# InkTime_Schematic.net
KiCad netlist of a schematic drawn in EAGLE
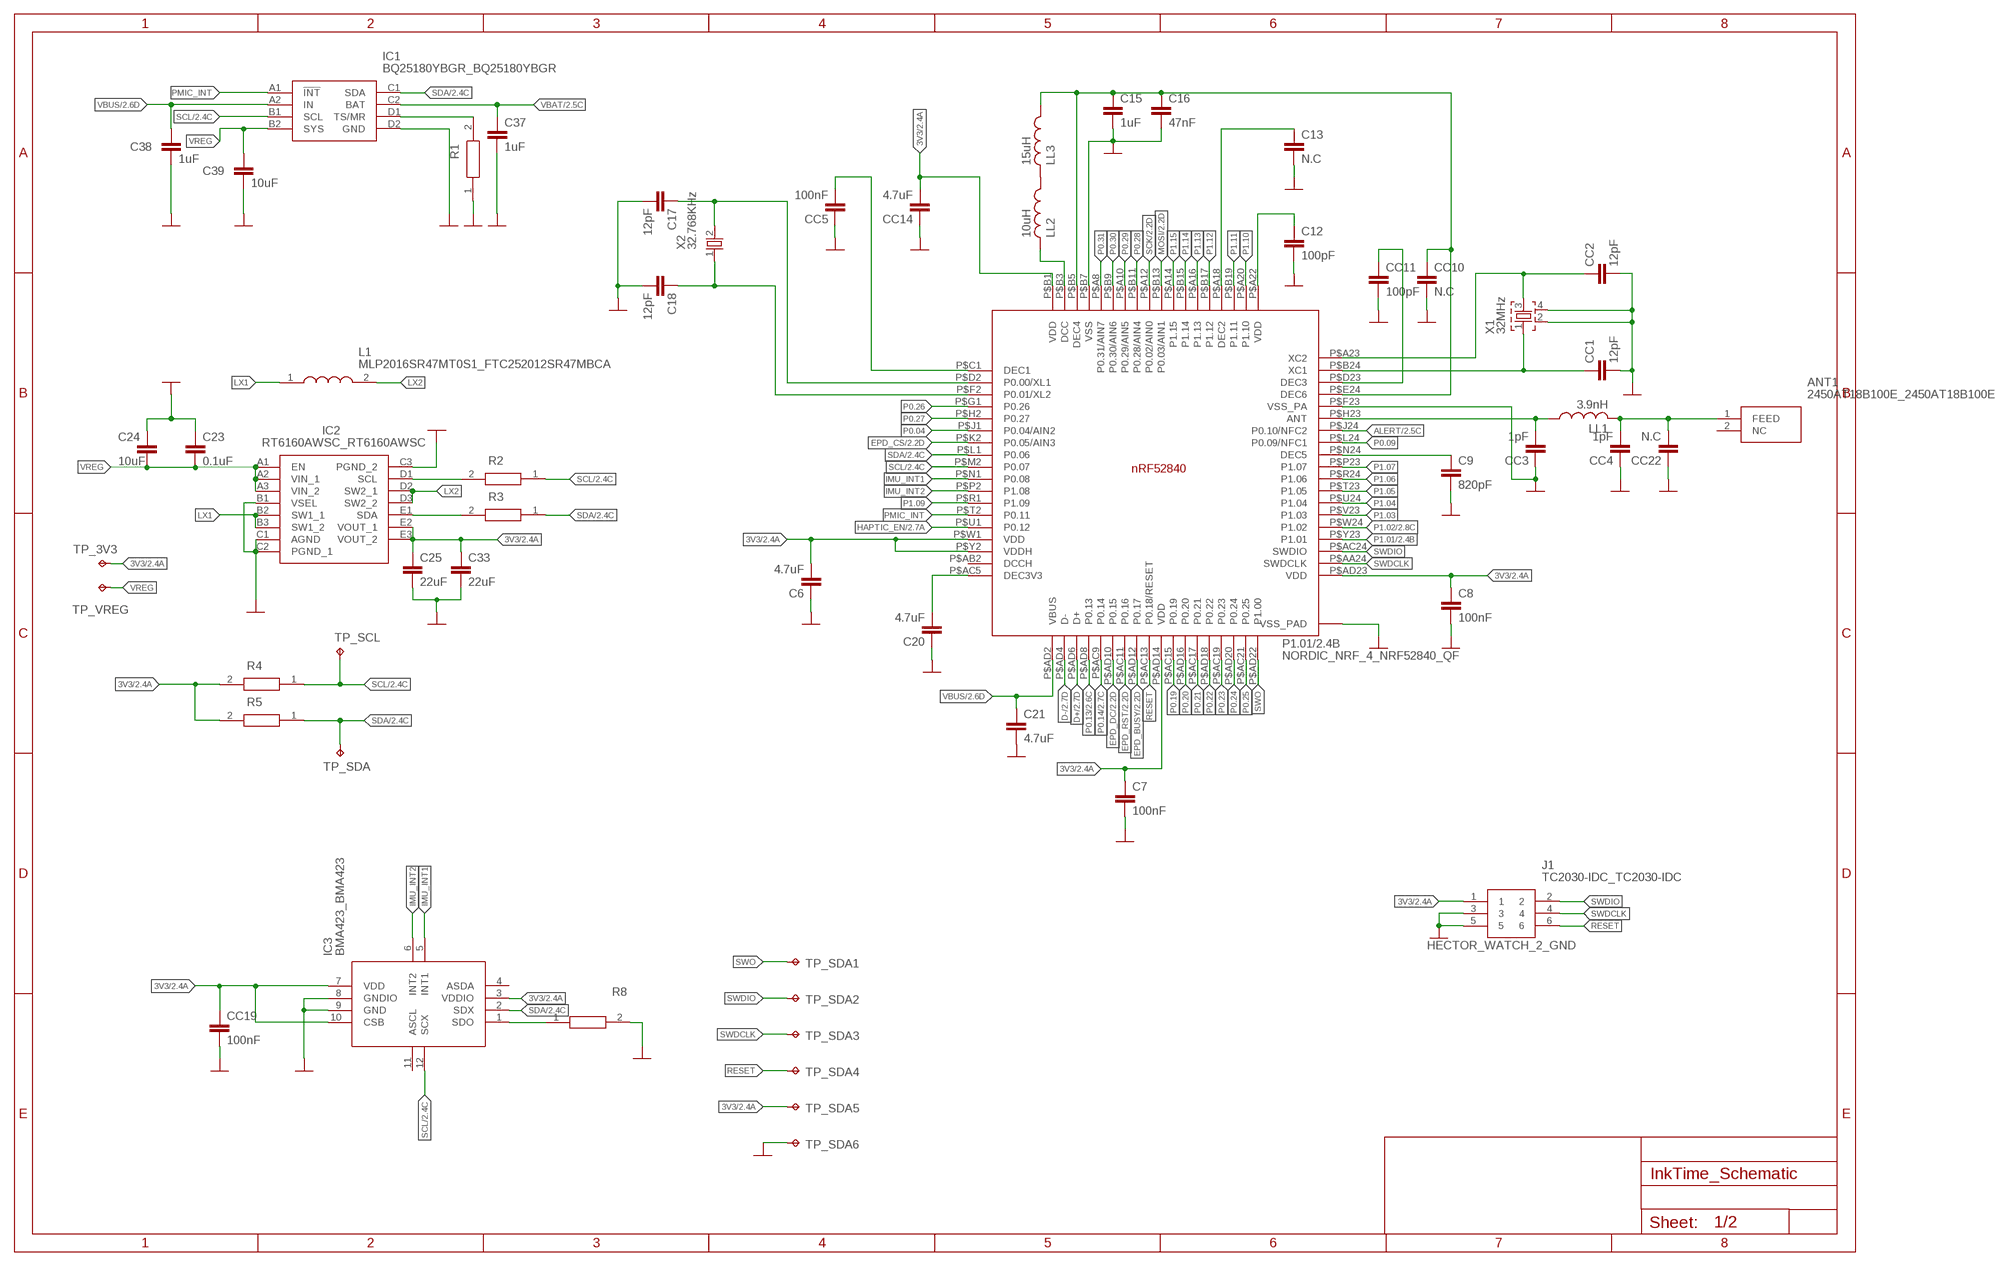
[diagram p0: schematic, sheet 1]
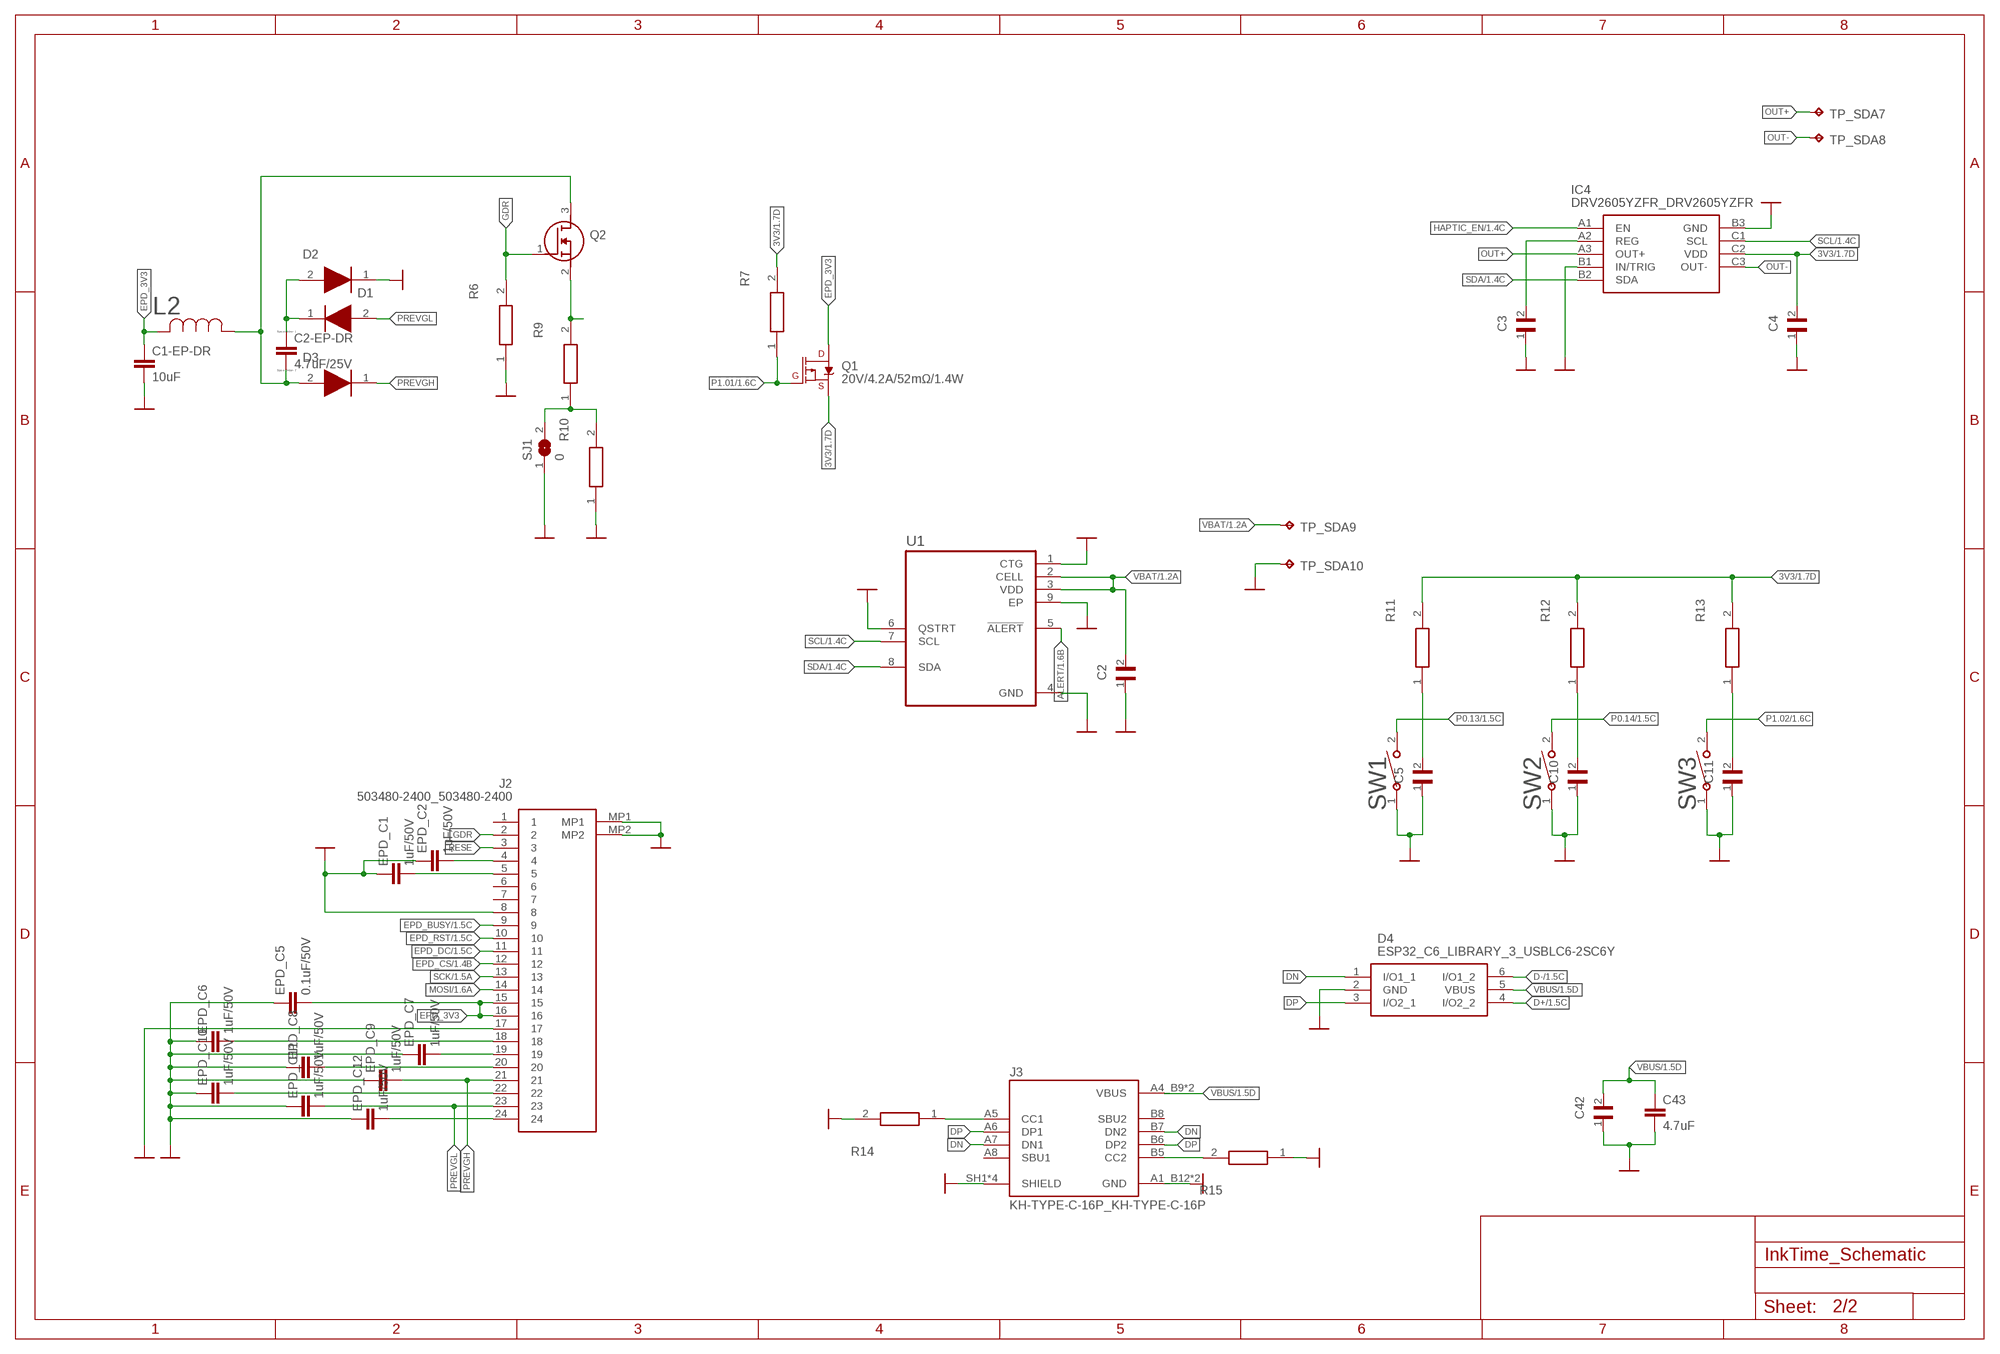
[diagram p1: schematic, sheet 2]

(export (version "E")
  (design (tool "Eeschema 10.0.6"))
  (components
    (comp (ref "ANT1")
      (value "2450AT18B100E_2450AT18B100E")
      (footprint "eagle-import:2450AT18B100E_ANTC3216X140N")
      (fields
        (field (name "ARROW_PART_NUMBER") "2450AT18B100E")
        (field (name "MOUSER_PART_NUMBER") "609-2450AT18B100E")
      )
      (libsource (lib "eagle-import") (part "2450AT18B100E_2450AT18B100E"))
    )
    (comp (ref "C6")
      (value "4.7uF")
      (footprint "eagle-import:NORDIC_NRF_3_RESC0402_M")
      (libsource (lib "eagle-import") (part "NORDIC_NRF_3_CAPACITOR_0402_M"))
    )
    (comp (ref "C7")
      (value "100nF")
      (footprint "eagle-import:NORDIC_NRF_3_RESC0402_M")
      (libsource (lib "eagle-import") (part "NORDIC_NRF_3_CAPACITOR_0402_M"))
    )
    (comp (ref "C8")
      (value "100nF")
      (footprint "eagle-import:NORDIC_NRF_3_RESC0402_M")
      (libsource (lib "eagle-import") (part "NORDIC_NRF_3_CAPACITOR_0402_M"))
    )
    (comp (ref "C9")
      (value "820pF")
      (footprint "eagle-import:NORDIC_NRF_3_RESC0402_M")
      (libsource (lib "eagle-import") (part "NORDIC_NRF_3_CAPACITOR_0402_M"))
    )
    (comp (ref "C12")
      (value "100pF")
      (footprint "eagle-import:NORDIC_NRF_3_RESC0402_M")
      (libsource (lib "eagle-import") (part "NORDIC_NRF_3_CAPACITOR_0402_M"))
    )
    (comp (ref "C13")
      (value "N.C")
      (footprint "eagle-import:NORDIC_NRF_3_RESC0402_M")
      (libsource (lib "eagle-import") (part "NORDIC_NRF_3_CAPACITOR_0402_M"))
    )
    (comp (ref "C15")
      (value "1uF")
      (footprint "eagle-import:NORDIC_NRF_3_RESC0402_M")
      (libsource (lib "eagle-import") (part "NORDIC_NRF_3_CAPACITOR_0402_M"))
    )
    (comp (ref "C16")
      (value "47nF")
      (footprint "eagle-import:NORDIC_NRF_3_RESC0402_M")
      (libsource (lib "eagle-import") (part "NORDIC_NRF_3_CAPACITOR_0402_M"))
    )
    (comp (ref "C17")
      (value "12pF")
      (footprint "eagle-import:NORDIC_NRF_3_RESC0402_M")
      (libsource (lib "eagle-import") (part "NORDIC_NRF_3_CAPACITOR_0402_M"))
    )
    (comp (ref "C18")
      (value "12pF")
      (footprint "eagle-import:NORDIC_NRF_3_RESC0402_M")
      (libsource (lib "eagle-import") (part "NORDIC_NRF_3_CAPACITOR_0402_M"))
    )
    (comp (ref "C20")
      (value "4.7uF")
      (footprint "eagle-import:NORDIC_NRF_3_RESC0402_M")
      (libsource (lib "eagle-import") (part "NORDIC_NRF_3_CAPACITOR_0402_M"))
    )
    (comp (ref "C21")
      (value "4.7uF")
      (footprint "eagle-import:NORDIC_NRF_3_RESC0402_M")
      (libsource (lib "eagle-import") (part "NORDIC_NRF_3_CAPACITOR_0402_M"))
    )
    (comp (ref "C23")
      (value "0.1uF")
      (footprint "eagle-import:NORDIC_NRF_3_RESC0402_M")
      (libsource (lib "eagle-import") (part "NORDIC_NRF_3_CAPACITOR_0402_M"))
    )
    (comp (ref "C24")
      (value "10uF")
      (footprint "eagle-import:NORDIC_NRF_3_RESC0402_M")
      (libsource (lib "eagle-import") (part "NORDIC_NRF_3_CAPACITOR_0402_M"))
    )
    (comp (ref "C25")
      (value "22uF")
      (footprint "eagle-import:NORDIC_NRF_3_RESC0402_M")
      (libsource (lib "eagle-import") (part "NORDIC_NRF_3_CAPACITOR_0402_M"))
    )
    (comp (ref "C33")
      (value "22uF")
      (footprint "eagle-import:NORDIC_NRF_3_RESC0402_M")
      (libsource (lib "eagle-import") (part "NORDIC_NRF_3_CAPACITOR_0402_M"))
    )
    (comp (ref "C37")
      (value "1uF")
      (footprint "eagle-import:NORDIC_NRF_3_RESC0402_M")
      (libsource (lib "eagle-import") (part "NORDIC_NRF_3_CAPACITOR_0402_M"))
    )
    (comp (ref "C38")
      (value "1uF")
      (footprint "eagle-import:NORDIC_NRF_3_RESC0402_M")
      (libsource (lib "eagle-import") (part "NORDIC_NRF_3_CAPACITOR_0402_M"))
    )
    (comp (ref "C39")
      (value "10uF")
      (footprint "eagle-import:NORDIC_NRF_3_RESC0402_M")
      (libsource (lib "eagle-import") (part "NORDIC_NRF_3_CAPACITOR_0402_M"))
    )
    (comp (ref "CC1")
      (value "12pF")
      (footprint "eagle-import:NORDIC_NRF_3_RESC0402_M")
      (libsource (lib "eagle-import") (part "NORDIC_NRF_3_CAPACITOR_0402_M"))
    )
    (comp (ref "CC2")
      (value "12pF")
      (footprint "eagle-import:NORDIC_NRF_3_RESC0402_M")
      (libsource (lib "eagle-import") (part "NORDIC_NRF_3_CAPACITOR_0402_M"))
    )
    (comp (ref "CC3")
      (value "1pF")
      (footprint "eagle-import:NORDIC_NRF_3_RESC0402_M")
      (libsource (lib "eagle-import") (part "NORDIC_NRF_3_CAPACITOR_0402_M"))
    )
    (comp (ref "CC4")
      (value "1pF")
      (footprint "eagle-import:NORDIC_NRF_3_RESC0402_M")
      (libsource (lib "eagle-import") (part "NORDIC_NRF_3_CAPACITOR_0402_M"))
    )
    (comp (ref "CC5")
      (value "100nF")
      (footprint "eagle-import:NORDIC_NRF_3_RESC0402_M")
      (libsource (lib "eagle-import") (part "NORDIC_NRF_3_CAPACITOR_0402_M"))
    )
    (comp (ref "CC10")
      (value "N.C")
      (footprint "eagle-import:NORDIC_NRF_3_RESC0402_M")
      (libsource (lib "eagle-import") (part "NORDIC_NRF_3_CAPACITOR_0402_M"))
    )
    (comp (ref "CC11")
      (value "100pF")
      (footprint "eagle-import:NORDIC_NRF_3_RESC0402_M")
      (libsource (lib "eagle-import") (part "NORDIC_NRF_3_CAPACITOR_0402_M"))
    )
    (comp (ref "CC14")
      (value "4.7uF")
      (footprint "eagle-import:NORDIC_NRF_3_RESC0402_M")
      (libsource (lib "eagle-import") (part "NORDIC_NRF_3_CAPACITOR_0402_M"))
    )
    (comp (ref "CC19")
      (value "100nF")
      (footprint "eagle-import:NORDIC_NRF_3_RESC0402_M")
      (libsource (lib "eagle-import") (part "NORDIC_NRF_3_CAPACITOR_0402_M"))
    )
    (comp (ref "CC22")
      (value "N.C")
      (footprint "eagle-import:NORDIC_NRF_3_RESC0402_M")
      (libsource (lib "eagle-import") (part "NORDIC_NRF_3_CAPACITOR_0402_M"))
    )
    (comp (ref "IC1")
      (value "BQ25180YBGR_BQ25180YBGR")
      (footprint "eagle-import:BQ25180YBGR_BGA8C40P2X4_100X155X50")
      (fields
        (field (name "ARROW_PART_NUMBER") "BQ25180YBGR")
        (field (name "MOUSER_PART_NUMBER") "595-BQ25180YBGR")
      )
      (libsource (lib "eagle-import") (part "BQ25180YBGR_BQ25180YBGR"))
    )
    (comp (ref "IC2")
      (value "RT6160AWSC_RT6160AWSC")
      (footprint "eagle-import:RT6160AWSC_BGA15C40P3X5_140X230X60")
      (fields
        (field (name "MANUFACTURER_PART_NUMBER") "RT6160AWSC")
        (field (name "MOUSER_PART_NUMBER") "835-RT6160AWSC")
      )
      (libsource (lib "eagle-import") (part "RT6160AWSC_RT6160AWSC"))
    )
    (comp (ref "IC3")
      (value "BMA423_BMA423")
      (footprint "eagle-import:BMA423_BMA423")
      (fields (field (name "ARROW_PART_NUMBER") "BMA423") (field (name "MOUSER_PART_NUMBER") "262-BMA423"))
      (libsource (lib "eagle-import") (part "BMA423_BMA423"))
    )
    (comp (ref "J1")
      (value "TC2030-IDC_TC2030-IDC")
      (footprint "eagle-import:TC2030-IDC_TC2030IDC")
      (fields (field (name "MANUFACTURER_PART_NUMBER") "TC2030-IDC"))
      (libsource (lib "eagle-import") (part "TC2030-IDC_TC2030-IDC"))
    )
    (comp (ref "L1")
      (value "MLP2016SR47MT0S1_FTC252012SR47MBCA")
      (footprint "eagle-import:MLP2016SR47MT0S1_INDC2016X100N")
      (fields (field (name "MANUFACTURER_PART_NUMBER") "FTC252012SR47MBCA"))
      (libsource (lib "eagle-import") (part "MLP2016SR47MT0S1_FTC252012SR47MBCA"))
    )
    (comp (ref "LL1")
      (value "3.9nH")
      (footprint "eagle-import:NORDIC_NRF_2_RESC0402_M")
      (libsource (lib "eagle-import") (part "NORDIC_NRF_2_INDUCTOR_0402_M"))
    )
    (comp (ref "LL2")
      (value "10uH")
      (footprint "eagle-import:NORDIC_NRF_2_RESC0402_M")
      (libsource (lib "eagle-import") (part "NORDIC_NRF_2_INDUCTOR_0402_M"))
    )
    (comp (ref "LL3")
      (value "15uH")
      (footprint "eagle-import:NORDIC_NRF_2_RESC0402_M")
      (libsource (lib "eagle-import") (part "NORDIC_NRF_2_INDUCTOR_0402_M"))
    )
    (comp (ref "P1.01/2.4B")
      (value "NORDIC_NRF_4_NRF52840_QF")
      (footprint "eagle-import:NORDIC_NRF_4_AQFN50P700X700X85_HS-74N")
      (libsource (lib "eagle-import") (part "NORDIC_NRF_4_NRF52840_QF"))
    )
    (comp (ref "R1")
      (value "10K")
      (footprint "eagle-import:CPF0201D7K68C1_0201")
      (libsource (lib "eagle-import") (part "CPF0201D7K68C1_CPF0201D7K68C1"))
    )
    (comp (ref "R2")
      (value "CPF0201D7K68C1_CPF0201D7K68C1")
      (footprint "eagle-import:CPF0201D7K68C1_0201")
      (libsource (lib "eagle-import") (part "CPF0201D7K68C1_CPF0201D7K68C1"))
    )
    (comp (ref "R3")
      (value "CPF0201D7K68C1_CPF0201D7K68C1")
      (footprint "eagle-import:CPF0201D7K68C1_0201")
      (libsource (lib "eagle-import") (part "CPF0201D7K68C1_CPF0201D7K68C1"))
    )
    (comp (ref "R4")
      (value "CPF0201D7K68C1_CPF0201D7K68C1")
      (footprint "eagle-import:CPF0201D7K68C1_0201")
      (libsource (lib "eagle-import") (part "CPF0201D7K68C1_CPF0201D7K68C1"))
    )
    (comp (ref "R5")
      (value "CPF0201D7K68C1_CPF0201D7K68C1")
      (footprint "eagle-import:CPF0201D7K68C1_0201")
      (libsource (lib "eagle-import") (part "CPF0201D7K68C1_CPF0201D7K68C1"))
    )
    (comp (ref "R8")
      (value "CPF0201D7K68C1_CPF0201D7K68C1")
      (footprint "eagle-import:CPF0201D7K68C1_0201")
      (libsource (lib "eagle-import") (part "CPF0201D7K68C1_CPF0201D7K68C1"))
    )
    (comp (ref "TP_3V3")
      (value "HECTOR_WATCH_1_TPTP20R")
      (footprint "eagle-import:HECTOR_WATCH_1_TP20R")
      (libsource (lib "eagle-import") (part "HECTOR_WATCH_1_TPTP20R"))
    )
    (comp (ref "TP_SCL")
      (value "HECTOR_WATCH_1_TPTP20R")
      (footprint "eagle-import:HECTOR_WATCH_1_TP20R")
      (libsource (lib "eagle-import") (part "HECTOR_WATCH_1_TPTP20R"))
    )
    (comp (ref "TP_SDA")
      (value "HECTOR_WATCH_1_TPTP20R")
      (footprint "eagle-import:HECTOR_WATCH_1_TP20R")
      (libsource (lib "eagle-import") (part "HECTOR_WATCH_1_TPTP20R"))
    )
    (comp (ref "TP_SDA1")
      (value "HECTOR_WATCH_1_TPTP20R")
      (footprint "eagle-import:HECTOR_WATCH_1_TP20R")
      (libsource (lib "eagle-import") (part "HECTOR_WATCH_1_TPTP20R"))
    )
    (comp (ref "TP_SDA2")
      (value "HECTOR_WATCH_1_TPTP20R")
      (footprint "eagle-import:HECTOR_WATCH_1_TP20R")
      (libsource (lib "eagle-import") (part "HECTOR_WATCH_1_TPTP20R"))
    )
    (comp (ref "TP_SDA3")
      (value "HECTOR_WATCH_1_TPTP20R")
      (footprint "eagle-import:HECTOR_WATCH_1_TP20R")
      (libsource (lib "eagle-import") (part "HECTOR_WATCH_1_TPTP20R"))
    )
    (comp (ref "TP_SDA4")
      (value "HECTOR_WATCH_1_TPTP20R")
      (footprint "eagle-import:HECTOR_WATCH_1_TP20R")
      (libsource (lib "eagle-import") (part "HECTOR_WATCH_1_TPTP20R"))
    )
    (comp (ref "TP_SDA5")
      (value "HECTOR_WATCH_1_TPTP20R")
      (footprint "eagle-import:HECTOR_WATCH_1_TP20R")
      (libsource (lib "eagle-import") (part "HECTOR_WATCH_1_TPTP20R"))
    )
    (comp (ref "TP_SDA6")
      (value "HECTOR_WATCH_1_TPTP20R")
      (footprint "eagle-import:HECTOR_WATCH_1_TP20R")
      (libsource (lib "eagle-import") (part "HECTOR_WATCH_1_TPTP20R"))
    )
    (comp (ref "TP_VREG")
      (value "HECTOR_WATCH_1_TPTP20R")
      (footprint "eagle-import:HECTOR_WATCH_1_TP20R")
      (libsource (lib "eagle-import") (part "HECTOR_WATCH_1_TPTP20R"))
    )
    (comp (ref "X1")
      (value "32MHz")
      (footprint "eagle-import:NORDIC_NRF_BT-XTAL_2016_N")
      (libsource (lib "eagle-import") (part "NORDIC_NRF_XTAL_32MHZ"))
    )
    (comp (ref "X2")
      (value "32.768KHz")
      (footprint "eagle-import:NORDIC_NRF_1_XTAL_3215_N")
      (libsource (lib "eagle-import") (part "NORDIC_NRF_1_XTAL_32KHZ"))
    )
    (comp (ref "C1-EP-DR")
      (value "10uF")
      (footprint "eagle-import:NORDIC_NRF_3_RESC0402_M")
      (libsource (lib "eagle-import") (part "NORDIC_NRF_3_CAPACITOR_0402_M"))
    )
    (comp (ref "C2")
      (value "GRM011R60J152KE01L_1_GRM011R60J152KE01L")
      (footprint "eagle-import:GRM011R60J152KE01L_1_0201")
      (libsource (lib "eagle-import") (part "GRM011R60J152KE01L_1_GRM011R60J152KE01L"))
    )
    (comp (ref "C2-EP-DR")
      (value "4.7uF/25V")
      (footprint "eagle-import:ESP32_C6_LIBRARY_1_ESP32_WROVER_EAGLE-LTSPICE_C0402")
      (libsource (lib "eagle-import") (part "ESP32_C6_LIBRARY_1_ESP32_WROVER_EAGLE-LTSPICE_CC0402"))
    )
    (comp (ref "C3")
      (value "1uF")
      (footprint "eagle-import:GRM011R60J152KE01L_1_0201")
      (libsource (lib "eagle-import") (part "GRM011R60J152KE01L_1_GRM011R60J152KE01L"))
    )
    (comp (ref "C4")
      (value "0.1uF")
      (footprint "eagle-import:GRM011R60J152KE01L_1_0201")
      (libsource (lib "eagle-import") (part "GRM011R60J152KE01L_1_GRM011R60J152KE01L"))
    )
    (comp (ref "C5")
      (value "GRM011R60J152KE01L_1_GRM011R60J152KE01L")
      (footprint "eagle-import:GRM011R60J152KE01L_1_0201")
      (libsource (lib "eagle-import") (part "GRM011R60J152KE01L_1_GRM011R60J152KE01L"))
    )
    (comp (ref "C10")
      (value "GRM011R60J152KE01L_1_GRM011R60J152KE01L")
      (footprint "eagle-import:GRM011R60J152KE01L_1_0201")
      (libsource (lib "eagle-import") (part "GRM011R60J152KE01L_1_GRM011R60J152KE01L"))
    )
    (comp (ref "C11")
      (value "GRM011R60J152KE01L_1_GRM011R60J152KE01L")
      (footprint "eagle-import:GRM011R60J152KE01L_1_0201")
      (libsource (lib "eagle-import") (part "GRM011R60J152KE01L_1_GRM011R60J152KE01L"))
    )
    (comp (ref "C42")
      (value "GRM011R60J152KE01L_1_GRM011R60J152KE01L")
      (footprint "eagle-import:GRM011R60J152KE01L_1_0201")
      (libsource (lib "eagle-import") (part "GRM011R60J152KE01L_1_GRM011R60J152KE01L"))
    )
    (comp (ref "C43")
      (value "4.7uF")
      (footprint "eagle-import:NORDIC_NRF_3_RESC0402_M")
      (libsource (lib "eagle-import") (part "NORDIC_NRF_3_CAPACITOR_0402_M"))
    )
    (comp (ref "D1")
      (value "ESP32_C6_LIBRARY_5_MBR0530")
      (footprint "eagle-import:ESP32_C6_LIBRARY_5_SOD3716X135N")
      (fields (field (name "MF") "ON Semiconductor") (field (name "MP") "MBR0530"))
      (libsource (lib "eagle-import") (part "ESP32_C6_LIBRARY_5_MBR0530"))
    )
    (comp (ref "D2")
      (value "ESP32_C6_LIBRARY_5_MBR0530")
      (footprint "eagle-import:ESP32_C6_LIBRARY_5_SOD3716X135N")
      (fields (field (name "MF") "ON Semiconductor") (field (name "MP") "MBR0530"))
      (libsource (lib "eagle-import") (part "ESP32_C6_LIBRARY_5_MBR0530"))
    )
    (comp (ref "D3")
      (value "ESP32_C6_LIBRARY_5_MBR0530")
      (footprint "eagle-import:ESP32_C6_LIBRARY_5_SOD3716X135N")
      (fields (field (name "MF") "ON Semiconductor") (field (name "MP") "MBR0530"))
      (libsource (lib "eagle-import") (part "ESP32_C6_LIBRARY_5_MBR0530"))
    )
    (comp (ref "D4")
      (value "ESP32_C6_LIBRARY_3_USBLC6-2SC6Y")
      (footprint "eagle-import:ESP32_C6_LIBRARY_3_SOT95P280X145-6N")
      (fields (field (name "MF") "STMicroelectronics") (field (name "MP") "USBLC6-2SC6Y"))
      (libsource (lib "eagle-import") (part "ESP32_C6_LIBRARY_3_USBLC6-2SC6Y"))
    )
    (comp (ref "EPD_C1")
      (value "1uF/50V")
      (footprint "eagle-import:NORDIC_NRF_3_RESC0402_M")
      (libsource (lib "eagle-import") (part "NORDIC_NRF_3_CAPACITOR_0402_M"))
    )
    (comp (ref "EPD_C2")
      (value "1uF/50V")
      (footprint "eagle-import:NORDIC_NRF_3_RESC0402_M")
      (libsource (lib "eagle-import") (part "NORDIC_NRF_3_CAPACITOR_0402_M"))
    )
    (comp (ref "EPD_C5")
      (value "0.1uF/50V")
      (footprint "eagle-import:NORDIC_NRF_3_RESC0402_M")
      (libsource (lib "eagle-import") (part "NORDIC_NRF_3_CAPACITOR_0402_M"))
    )
    (comp (ref "EPD_C6")
      (value "1uF/50V")
      (footprint "eagle-import:NORDIC_NRF_3_RESC0402_M")
      (libsource (lib "eagle-import") (part "NORDIC_NRF_3_CAPACITOR_0402_M"))
    )
    (comp (ref "EPD_C7")
      (value "1uF/50V")
      (footprint "eagle-import:NORDIC_NRF_3_RESC0402_M")
      (libsource (lib "eagle-import") (part "NORDIC_NRF_3_CAPACITOR_0402_M"))
    )
    (comp (ref "EPD_C8")
      (value "1uF/50V")
      (footprint "eagle-import:NORDIC_NRF_3_RESC0402_M")
      (libsource (lib "eagle-import") (part "NORDIC_NRF_3_CAPACITOR_0402_M"))
    )
    (comp (ref "EPD_C9")
      (value "1uF/50V")
      (footprint "eagle-import:NORDIC_NRF_3_RESC0402_M")
      (libsource (lib "eagle-import") (part "NORDIC_NRF_3_CAPACITOR_0402_M"))
    )
    (comp (ref "EPD_C10")
      (value "1uF/50V")
      (footprint "eagle-import:NORDIC_NRF_3_RESC0402_M")
      (libsource (lib "eagle-import") (part "NORDIC_NRF_3_CAPACITOR_0402_M"))
    )
    (comp (ref "EPD_C11")
      (value "1uF/50V")
      (footprint "eagle-import:NORDIC_NRF_3_RESC0402_M")
      (libsource (lib "eagle-import") (part "NORDIC_NRF_3_CAPACITOR_0402_M"))
    )
    (comp (ref "EPD_C12")
      (value "1uF/50V")
      (footprint "eagle-import:NORDIC_NRF_3_RESC0402_M")
      (libsource (lib "eagle-import") (part "NORDIC_NRF_3_CAPACITOR_0402_M"))
    )
    (comp (ref "IC4")
      (value "DRV2605YZFR_DRV2605YZFR")
      (footprint "eagle-import:DRV2605YZFR_BGA9C50P3X3_144X144X62")
      (fields (field (name "ARROW_PART_NUMBER") "DRV2605YZFR"))
      (libsource (lib "eagle-import") (part "DRV2605YZFR_DRV2605YZFR"))
    )
    (comp (ref "J2")
      (value "503480-2400_503480-2400")
      (footprint "eagle-import:503480-2400_5034802400")
      (fields
        (field (name "MANUFACTURER_PART_NUMBER") "503480-2400")
        (field (name "MOUSER_PART_NUMBER") "538-503480-2400")
      )
      (libsource (lib "eagle-import") (part "503480-2400_503480-2400"))
    )
    (comp (ref "J3")
      (value "KH-TYPE-C-16P_KH-TYPE-C-16P")
      (footprint "eagle-import:KH-TYPE-C-16P_KINGHELM_KH-TYPE-C-16P")
      (fields (field (name "MF") "kinghelm") (field (name "MP") "KH-TYPE-C-16P"))
      (libsource (lib "eagle-import") (part "KH-TYPE-C-16P_KH-TYPE-C-16P"))
    )
    (comp (ref "L2")
      (value "ESP32_C6_LIBRARY_2_744043680IND_4828-WE-TPC_WRE")
      (footprint "eagle-import:ESP32_C6_LIBRARY_2_IND_4828-WE-TPC_WRE")
      (fields
        (field (name "MANUFACTURER_PART_NUMBER") "744043680")
        (field (name "COPYRIGHT") "Copyright (C) 2024 Ultra Librarian. All rights reserved.")
      )
      (libsource (lib "eagle-import") (part "ESP32_C6_LIBRARY_2_744043680IND_4828-WE-TPC_WRE"))
    )
    (comp (ref "Q1")
      (value "20V/4.2A/52mΩ/1.4W")
      (footprint "eagle-import:ESP32_C6_LIBRARY_4_ESP32_C6_LIBRARY_4_ESP32_C6_LIBRARY_4_ESP32_C6_LIBRARY_4_ESP32_WROVER_SPARKFUN-DISCRETESEMI_SOT23-3")
      (libsource (lib "eagle-import") (part "ESP32_C6_LIBRARY_4_ESP32_WROVER_SPARKFUN-DISCRETESEMI_MOSFET_PCH-DMG2305UX-7"))
    )
    (comp (ref "Q2")
      (value "ESP32_C6_LIBRARY_6_SI1308EDL-T1-GE3")
      (footprint "eagle-import:ESP32_C6_LIBRARY_6_SOT65P210X110-3N")
      (fields (field (name "MF") "Vishay Siliconix") (field (name "MP") "SI1308EDL-T1-GE3"))
      (libsource (lib "eagle-import") (part "ESP32_C6_LIBRARY_6_SI1308EDL-T1-GE3"))
    )
    (comp (ref "R6")
      (value "CPF0201D7K68C1_CPF0201D7K68C1")
      (footprint "eagle-import:CPF0201D7K68C1_0201")
      (libsource (lib "eagle-import") (part "CPF0201D7K68C1_CPF0201D7K68C1"))
    )
    (comp (ref "R7")
      (value "CPF0201D7K68C1_CPF0201D7K68C1")
      (footprint "eagle-import:CPF0201D7K68C1_0201")
      (libsource (lib "eagle-import") (part "CPF0201D7K68C1_CPF0201D7K68C1"))
    )
    (comp (ref "R9")
      (value "CPF0201D7K68C1_CPF0201D7K68C1")
      (footprint "eagle-import:CPF0201D7K68C1_0201")
      (libsource (lib "eagle-import") (part "CPF0201D7K68C1_CPF0201D7K68C1"))
    )
    (comp (ref "R10")
      (value "CPF0201D7K68C1_CPF0201D7K68C1")
      (footprint "eagle-import:CPF0201D7K68C1_0201")
      (libsource (lib "eagle-import") (part "CPF0201D7K68C1_CPF0201D7K68C1"))
    )
    (comp (ref "R11")
      (value "CPF0201D7K68C1_CPF0201D7K68C1")
      (footprint "eagle-import:CPF0201D7K68C1_0201")
      (libsource (lib "eagle-import") (part "CPF0201D7K68C1_CPF0201D7K68C1"))
    )
    (comp (ref "R12")
      (value "CPF0201D7K68C1_CPF0201D7K68C1")
      (footprint "eagle-import:CPF0201D7K68C1_0201")
      (libsource (lib "eagle-import") (part "CPF0201D7K68C1_CPF0201D7K68C1"))
    )
    (comp (ref "R13")
      (value "CPF0201D7K68C1_CPF0201D7K68C1")
      (footprint "eagle-import:CPF0201D7K68C1_0201")
      (libsource (lib "eagle-import") (part "CPF0201D7K68C1_CPF0201D7K68C1"))
    )
    (comp (ref "R14")
      (value "CPF0201D7K68C1_CPF0201D7K68C1")
      (footprint "eagle-import:CPF0201D7K68C1_0201")
      (libsource (lib "eagle-import") (part "CPF0201D7K68C1_CPF0201D7K68C1"))
    )
    (comp (ref "R15")
      (value "CPF0201D7K68C1_CPF0201D7K68C1")
      (footprint "eagle-import:CPF0201D7K68C1_0201")
      (libsource (lib "eagle-import") (part "CPF0201D7K68C1_CPF0201D7K68C1"))
    )
    (comp (ref "SJ1")
      (value "0")
      (footprint "eagle-import:ESP32_C6_LIBRARY_7_JUMPER_SJ")
      (libsource (lib "eagle-import") (part "ESP32_C6_LIBRARY_7_JUMPER_SJ"))
    )
    (comp (ref "SW1")
      (value "2025-10-22_07-23-44_LIBRARY_EVP-AKE31ASW_EVP-AKE31A_PAN")
      (footprint "eagle-import:2025-10-22_07-23-44_LIBRARY_SW_EVP-AKE31A_PAN")
      (fields
        (field (name "MANUFACTURER_PART_NUMBER") "EVP-AKE31A")
        (field (name "COPYRIGHT") "Copyright (C) 2025 Ultra Librarian. All rights reserved.")
      )
      (libsource (lib "eagle-import") (part "2025-10-22_07-23-44_LIBRARY_EVP-AKE31ASW_EVP-AKE31A_PAN"))
    )
    (comp (ref "SW2")
      (value "2025-10-22_07-23-44_LIBRARY_EVP-AKE31ASW_EVP-AKE31A_PAN")
      (footprint "eagle-import:2025-10-22_07-23-44_LIBRARY_SW_EVP-AKE31A_PAN")
      (fields
        (field (name "MANUFACTURER_PART_NUMBER") "EVP-AKE31A")
        (field (name "COPYRIGHT") "Copyright (C) 2025 Ultra Librarian. All rights reserved.")
      )
      (libsource (lib "eagle-import") (part "2025-10-22_07-23-44_LIBRARY_EVP-AKE31ASW_EVP-AKE31A_PAN"))
    )
    (comp (ref "SW3")
      (value "2025-10-22_07-23-44_LIBRARY_EVP-AKE31ASW_EVP-AKE31A_PAN")
      (footprint "eagle-import:2025-10-22_07-23-44_LIBRARY_SW_EVP-AKE31A_PAN")
      (fields
        (field (name "MANUFACTURER_PART_NUMBER") "EVP-AKE31A")
        (field (name "COPYRIGHT") "Copyright (C) 2025 Ultra Librarian. All rights reserved.")
      )
      (libsource (lib "eagle-import") (part "2025-10-22_07-23-44_LIBRARY_EVP-AKE31ASW_EVP-AKE31A_PAN"))
    )
    (comp (ref "TP_SDA7")
      (value "HECTOR_WATCH_1_TPTP20R")
      (footprint "eagle-import:HECTOR_WATCH_1_TP20R")
      (libsource (lib "eagle-import") (part "HECTOR_WATCH_1_TPTP20R"))
    )
    (comp (ref "TP_SDA8")
      (value "HECTOR_WATCH_1_TPTP20R")
      (footprint "eagle-import:HECTOR_WATCH_1_TP20R")
      (libsource (lib "eagle-import") (part "HECTOR_WATCH_1_TPTP20R"))
    )
    (comp (ref "TP_SDA9")
      (value "HECTOR_WATCH_1_TPTP20R")
      (footprint "eagle-import:HECTOR_WATCH_1_TP20R")
      (libsource (lib "eagle-import") (part "HECTOR_WATCH_1_TPTP20R"))
    )
    (comp (ref "TP_SDA10")
      (value "HECTOR_WATCH_1_TPTP20R")
      (footprint "eagle-import:HECTOR_WATCH_1_TP20R")
      (libsource (lib "eagle-import") (part "HECTOR_WATCH_1_TPTP20R"))
    )
    (comp (ref "U1")
      (value "ESP32_C6_LIBRARY_MAX17048G+T10")
      (footprint "eagle-import:ESP32_C6_LIBRARY_SON50P200X200X80-9N")
      (fields (field (name "MF") "Analog Devices") (field (name "MP") "MAX17048G+T10"))
      (libsource (lib "eagle-import") (part "ESP32_C6_LIBRARY_MAX17048G+T10"))
    )
  )
  (nets
    (net (code "1") (name "3V3{slash}1.7D") (class "Default")
      (node (ref "C4") (pin "2") (pinfunction "2_2") (pintype "passive"))
      (node (ref "IC4") (pin "C2") (pinfunction "VDD_C2") (pintype "bidirectional"))
      (node (ref "Q1") (pin "2") (pinfunction "S_2") (pintype "bidirectional"))
      (node (ref "R11") (pin "2") (pinfunction "2_2") (pintype "bidirectional"))
      (node (ref "R12") (pin "2") (pinfunction "2_2") (pintype "bidirectional"))
      (node (ref "R13") (pin "2") (pinfunction "2_2") (pintype "bidirectional"))
      (node (ref "R7") (pin "2") (pinfunction "2_2") (pintype "bidirectional"))
    )
    (net (code "2") (name "3V3{slash}2.4A") (class "Default")
      (node (ref "C25") (pin "1") (pinfunction "1_1") (pintype "passive"))
      (node (ref "C33") (pin "1") (pinfunction "1_1") (pintype "passive"))
      (node (ref "C6") (pin "2") (pinfunction "2_2") (pintype "passive"))
      (node (ref "C7") (pin "1") (pinfunction "1_1") (pintype "passive"))
      (node (ref "C8") (pin "1") (pinfunction "1_1") (pintype "passive"))
      (node (ref "CC14") (pin "2") (pinfunction "2_2") (pintype "passive"))
      (node (ref "CC19") (pin "1") (pinfunction "1_1") (pintype "passive"))
      (node (ref "IC2") (pin "E2") (pinfunction "VOUT_1_E2") (pintype "bidirectional"))
      (node (ref "IC2") (pin "E3") (pinfunction "VOUT_2_E3") (pintype "bidirectional"))
      (node (ref "IC3") (pin "10") (pinfunction "CSB_10") (pintype "bidirectional"))
      (node (ref "IC3") (pin "3") (pinfunction "VDDIO_3") (pintype "bidirectional"))
      (node (ref "IC3") (pin "7") (pinfunction "VDD_7") (pintype "bidirectional"))
      (node (ref "J1") (pin "1") (pinfunction "1_1") (pintype "bidirectional"))
      (node (ref "P1.01/2.4B") (pin "P$AD14") (pinfunction "VDD_P$AD14") (pintype "power_in"))
      (node (ref "P1.01/2.4B") (pin "P$AD23") (pinfunction "VDD_P$AD23") (pintype "power_in"))
      (node (ref "P1.01/2.4B") (pin "P$B1") (pinfunction "VDD_P$B1") (pintype "power_in"))
      (node (ref "P1.01/2.4B") (pin "P$W1") (pinfunction "VDD_P$W1") (pintype "power_in"))
      (node (ref "P1.01/2.4B") (pin "P$Y2") (pinfunction "VDDH_P$Y2") (pintype "power_in"))
      (node (ref "R4") (pin "2") (pinfunction "2_2") (pintype "bidirectional"))
      (node (ref "R5") (pin "2") (pinfunction "2_2") (pintype "bidirectional"))
      (node (ref "TP_3V3") (pin "TP") (pinfunction "TP_TP") (pintype "input"))
      (node (ref "TP_SDA5") (pin "TP") (pinfunction "TP_TP") (pintype "input"))
    )
    (net (code "3") (name "ALERT") (class "Default")
      (node (ref "P1.01/2.4B") (pin "P$J24") (pinfunction "P0.10/NFC2_P$J24") (pintype "bidirectional"))
      (node (ref "U1") (pin "5") (pinfunction "~{ALERT}_5") (pintype "output"))
    )
    (net (code "4") (name "D+") (class "Default")
      (node (ref "D4") (pin "4") (pinfunction "I/O2_2_4") (pintype "bidirectional"))
      (node (ref "P1.01/2.4B") (pin "P$AD6") (pinfunction "D+_P$AD6") (pintype "bidirectional"))
    )
    (net (code "5") (name "D-") (class "Default")
      (node (ref "D4") (pin "6") (pinfunction "I/O1_2_6") (pintype "bidirectional"))
      (node (ref "P1.01/2.4B") (pin "P$AD4") (pinfunction "D-_P$AD4") (pintype "bidirectional"))
    )
    (net (code "6") (name "DN") (class "Default")
      (node (ref "D4") (pin "1") (pinfunction "I/O1_1_1") (pintype "bidirectional"))
      (node (ref "J3") (pin "A7") (pinfunction "DN1_A7") (pintype "bidirectional"))
      (node (ref "J3") (pin "B7") (pinfunction "DN2_B7") (pintype "bidirectional"))
    )
    (net (code "7") (name "DP") (class "Default")
      (node (ref "D4") (pin "3") (pinfunction "I/O2_1_3") (pintype "bidirectional"))
      (node (ref "J3") (pin "A6") (pinfunction "DP1_A6") (pintype "bidirectional"))
      (node (ref "J3") (pin "B6") (pinfunction "DP2_B6") (pintype "bidirectional"))
    )
    (net (code "8") (name "EPD_3V3") (class "Default")
      (node (ref "C1-EP-DR") (pin "1") (pinfunction "1_1") (pintype "passive"))
      (node (ref "EPD_C5") (pin "2") (pinfunction "2_2") (pintype "passive"))
      (node (ref "J2") (pin "15") (pinfunction "15_15") (pintype "bidirectional"))
      (node (ref "J2") (pin "16") (pinfunction "16_16") (pintype "bidirectional"))
      (node (ref "L2") (pin "2") (pinfunction "2_2") (pintype "passive"))
      (node (ref "Q1") (pin "3") (pinfunction "D_3") (pintype "bidirectional"))
    )
    (net (code "9") (name "EPD_BUSY") (class "Default")
      (node (ref "J2") (pin "9") (pinfunction "9_9") (pintype "bidirectional"))
      (node (ref "P1.01/2.4B") (pin "P$AD12") (pinfunction "P0.17_P$AD12") (pintype "bidirectional"))
    )
    (net (code "10") (name "EPD_CS") (class "Default")
      (node (ref "J2") (pin "12") (pinfunction "12_12") (pintype "bidirectional"))
      (node (ref "P1.01/2.4B") (pin "P$K2") (pinfunction "P0.05/AIN3_P$K2") (pintype "bidirectional"))
    )
    (net (code "11") (name "EPD_DC") (class "Default")
      (node (ref "J2") (pin "11") (pinfunction "11_11") (pintype "bidirectional"))
      (node (ref "P1.01/2.4B") (pin "P$AD10") (pinfunction "P0.15_P$AD10") (pintype "bidirectional"))
    )
    (net (code "12") (name "EPD_RST") (class "Default")
      (node (ref "J2") (pin "10") (pinfunction "10_10") (pintype "bidirectional"))
      (node (ref "P1.01/2.4B") (pin "P$AC11") (pinfunction "P0.16_P$AC11") (pintype "bidirectional"))
    )
    (net (code "13") (name "GDR") (class "Default")
      (node (ref "J2") (pin "2") (pinfunction "2_2") (pintype "bidirectional"))
      (node (ref "Q2") (pin "1") (pinfunction "G_1") (pintype "bidirectional"))
      (node (ref "R6") (pin "2") (pinfunction "2_2") (pintype "bidirectional"))
    )
    (net (code "14") (name "GND") (class "Default")
      (node (ref "C1-EP-DR") (pin "2") (pinfunction "2_2") (pintype "passive"))
      (node (ref "C10") (pin "1") (pinfunction "1_1") (pintype "passive"))
      (node (ref "C11") (pin "1") (pinfunction "1_1") (pintype "passive"))
      (node (ref "C12") (pin "2") (pinfunction "2_2") (pintype "passive"))
      (node (ref "C13") (pin "2") (pinfunction "2_2") (pintype "passive"))
      (node (ref "C15") (pin "2") (pinfunction "2_2") (pintype "passive"))
      (node (ref "C16") (pin "2") (pinfunction "2_2") (pintype "passive"))
      (node (ref "C17") (pin "2") (pinfunction "2_2") (pintype "passive"))
      (node (ref "C18") (pin "2") (pinfunction "2_2") (pintype "passive"))
      (node (ref "C2") (pin "1") (pinfunction "1_1") (pintype "passive"))
      (node (ref "C20") (pin "1") (pinfunction "1_1") (pintype "passive"))
      (node (ref "C21") (pin "2") (pinfunction "2_2") (pintype "passive"))
      (node (ref "C23") (pin "1") (pinfunction "1_1") (pintype "passive"))
      (node (ref "C24") (pin "1") (pinfunction "1_1") (pintype "passive"))
      (node (ref "C25") (pin "2") (pinfunction "2_2") (pintype "passive"))
      (node (ref "C3") (pin "1") (pinfunction "1_1") (pintype "passive"))
      (node (ref "C33") (pin "2") (pinfunction "2_2") (pintype "passive"))
      (node (ref "C37") (pin "2") (pinfunction "2_2") (pintype "passive"))
      (node (ref "C38") (pin "2") (pinfunction "2_2") (pintype "passive"))
      (node (ref "C39") (pin "2") (pinfunction "2_2") (pintype "passive"))
      (node (ref "C4") (pin "1") (pinfunction "1_1") (pintype "passive"))
      (node (ref "C42") (pin "1") (pinfunction "1_1") (pintype "passive"))
      (node (ref "C43") (pin "2") (pinfunction "2_2") (pintype "passive"))
      (node (ref "C5") (pin "1") (pinfunction "1_1") (pintype "passive"))
      (node (ref "C6") (pin "1") (pinfunction "1_1") (pintype "passive"))
      (node (ref "C7") (pin "2") (pinfunction "2_2") (pintype "passive"))
      (node (ref "C8") (pin "2") (pinfunction "2_2") (pintype "passive"))
      (node (ref "C9") (pin "2") (pinfunction "2_2") (pintype "passive"))
      (node (ref "CC1") (pin "2") (pinfunction "2_2") (pintype "passive"))
      (node (ref "CC10") (pin "2") (pinfunction "2_2") (pintype "passive"))
      (node (ref "CC11") (pin "2") (pinfunction "2_2") (pintype "passive"))
      (node (ref "CC14") (pin "1") (pinfunction "1_1") (pintype "passive"))
      (node (ref "CC19") (pin "2") (pinfunction "2_2") (pintype "passive"))
      (node (ref "CC2") (pin "2") (pinfunction "2_2") (pintype "passive"))
      (node (ref "CC22") (pin "1") (pinfunction "1_1") (pintype "passive"))
      (node (ref "CC3") (pin "1") (pinfunction "1_1") (pintype "passive"))
      (node (ref "CC4") (pin "1") (pinfunction "1_1") (pintype "passive"))
      (node (ref "CC5") (pin "1") (pinfunction "1_1") (pintype "passive"))
      (node (ref "D2") (pin "1") (pinfunction "K_1") (pintype "bidirectional"))
      (node (ref "D4") (pin "2") (pinfunction "GND_2") (pintype "bidirectional"))
      (node (ref "EPD_C1") (pin "1") (pinfunction "1_1") (pintype "passive"))
      (node (ref "EPD_C10") (pin "1") (pinfunction "1_1") (pintype "passive"))
      (node (ref "EPD_C11") (pin "1") (pinfunction "1_1") (pintype "passive"))
      (node (ref "EPD_C12") (pin "1") (pinfunction "1_1") (pintype "passive"))
      (node (ref "EPD_C2") (pin "1") (pinfunction "1_1") (pintype "passive"))
      (node (ref "EPD_C5") (pin "1") (pinfunction "1_1") (pintype "passive"))
      (node (ref "EPD_C6") (pin "1") (pinfunction "1_1") (pintype "passive"))
      (node (ref "EPD_C7") (pin "1") (pinfunction "1_1") (pintype "passive"))
      (node (ref "EPD_C8") (pin "1") (pinfunction "1_1") (pintype "passive"))
      (node (ref "EPD_C9") (pin "1") (pinfunction "1_1") (pintype "passive"))
      (node (ref "IC1") (pin "D2") (pinfunction "GND_D2") (pintype "bidirectional"))
      (node (ref "IC2") (pin "B1") (pinfunction "VSEL_B1") (pintype "bidirectional"))
      (node (ref "IC2") (pin "C1") (pinfunction "AGND_C1") (pintype "bidirectional"))
      (node (ref "IC2") (pin "C2") (pinfunction "PGND_1_C2") (pintype "bidirectional"))
      (node (ref "IC2") (pin "C3") (pinfunction "PGND_2_C3") (pintype "bidirectional"))
      (node (ref "IC3") (pin "8") (pinfunction "GNDIO_8") (pintype "bidirectional"))
      (node (ref "IC3") (pin "9") (pinfunction "GND_9") (pintype "bidirectional"))
      (node (ref "IC4") (pin "B1") (pinfunction "IN/TRIG_B1") (pintype "bidirectional"))
      (node (ref "IC4") (pin "B3") (pinfunction "GND_B3") (pintype "bidirectional"))
      (node (ref "J1") (pin "3") (pinfunction "3_3") (pintype "bidirectional"))
      (node (ref "J1") (pin "5") (pinfunction "5_5") (pintype "bidirectional"))
      (node (ref "J2") (pin "17") (pinfunction "17_17") (pintype "bidirectional"))
      (node (ref "J2") (pin "8") (pinfunction "8_8") (pintype "bidirectional"))
      (node (ref "J2") (pin "MP1") (pinfunction "MP1_MP1") (pintype "bidirectional"))
      (node (ref "J2") (pin "MP2") (pinfunction "MP2_MP2") (pintype "bidirectional"))
      (node (ref "J3") (pin "A12_B1") (pinfunction "GND_A12_B1") (pintype "power_in"))
      (node (ref "J3") (pin "A1_B12") (pinfunction "GND_A1_B12") (pintype "power_in"))
      (node (ref "J3") (pin "SH1") (pinfunction "SHIELD_SH1") (pintype "passive"))
      (node (ref "J3") (pin "SH2") (pinfunction "SHIELD_SH2") (pintype "passive"))
      (node (ref "J3") (pin "SH3") (pinfunction "SHIELD_SH3") (pintype "passive"))
      (node (ref "J3") (pin "SH4") (pinfunction "SHIELD_SH4") (pintype "passive"))
      (node (ref "P1.01/2.4B") (pin "P$74") (pinfunction "VSS_PAD_P$74") (pintype "bidirectional"))
      (node (ref "P1.01/2.4B") (pin "P$75") (pinfunction "VSS_PAD_P$75") (pintype "bidirectional"))
      (node (ref "P1.01/2.4B") (pin "P$76") (pinfunction "VSS_PAD_P$76") (pintype "bidirectional"))
      (node (ref "P1.01/2.4B") (pin "P$77") (pinfunction "VSS_PAD_P$77") (pintype "bidirectional"))
      (node (ref "P1.01/2.4B") (pin "P$78") (pinfunction "VSS_PAD_P$78") (pintype "bidirectional"))
      (node (ref "P1.01/2.4B") (pin "P$79") (pinfunction "VSS_PAD_P$79") (pintype "bidirectional"))
      (node (ref "P1.01/2.4B") (pin "P$80") (pinfunction "VSS_PAD_P$80") (pintype "bidirectional"))
      (node (ref "P1.01/2.4B") (pin "P$81") (pinfunction "VSS_PAD_P$81") (pintype "bidirectional"))
      (node (ref "P1.01/2.4B") (pin "P$82") (pinfunction "VSS_PAD_P$82") (pintype "bidirectional"))
      (node (ref "P1.01/2.4B") (pin "P$83") (pinfunction "VSS_PAD_P$83") (pintype "bidirectional"))
      (node (ref "P1.01/2.4B") (pin "P$84") (pinfunction "VSS_PAD_P$84") (pintype "bidirectional"))
      (node (ref "P1.01/2.4B") (pin "P$85") (pinfunction "VSS_PAD_P$85") (pintype "bidirectional"))
      (node (ref "P1.01/2.4B") (pin "P$86") (pinfunction "VSS_PAD_P$86") (pintype "bidirectional"))
      (node (ref "P1.01/2.4B") (pin "P$87") (pinfunction "VSS_PAD_P$87") (pintype "bidirectional"))
      (node (ref "P1.01/2.4B") (pin "P$88") (pinfunction "VSS_PAD_P$88") (pintype "bidirectional"))
      (node (ref "P1.01/2.4B") (pin "P$89") (pinfunction "VSS_PAD_P$89") (pintype "bidirectional"))
      (node (ref "P1.01/2.4B") (pin "P$90") (pinfunction "VSS_PAD_P$90") (pintype "bidirectional"))
      (node (ref "P1.01/2.4B") (pin "P$B7") (pinfunction "VSS_P$B7") (pintype "power_in"))
      (node (ref "P1.01/2.4B") (pin "P$F23") (pinfunction "VSS_PA_P$F23") (pintype "bidirectional"))
      (node (ref "R1") (pin "1") (pinfunction "1_1") (pintype "bidirectional"))
      (node (ref "R10") (pin "1") (pinfunction "1_1") (pintype "bidirectional"))
      (node (ref "R14") (pin "2") (pinfunction "2_2") (pintype "bidirectional"))
      (node (ref "R15") (pin "1") (pinfunction "1_1") (pintype "bidirectional"))
      (node (ref "R6") (pin "1") (pinfunction "1_1") (pintype "bidirectional"))
      (node (ref "R8") (pin "2") (pinfunction "2_2") (pintype "bidirectional"))
      (node (ref "SJ1") (pin "1") (pinfunction "1_1") (pintype "passive"))
      (node (ref "SW1") (pin "1") (pinfunction "1_1") (pintype "passive"))
      (node (ref "SW2") (pin "1") (pinfunction "1_1") (pintype "passive"))
      (node (ref "SW3") (pin "1") (pinfunction "1_1") (pintype "passive"))
      (node (ref "TP_SDA10") (pin "TP") (pinfunction "TP_TP") (pintype "input"))
      (node (ref "TP_SDA6") (pin "TP") (pinfunction "TP_TP") (pintype "input"))
      (node (ref "U1") (pin "1") (pinfunction "CTG_1") (pintype "power_in"))
      (node (ref "U1") (pin "4") (pinfunction "GND_4") (pintype "power_in"))
      (node (ref "U1") (pin "6") (pinfunction "QSTRT_6") (pintype "input"))
      (node (ref "U1") (pin "9") (pinfunction "EP_9") (pintype "power_in"))
      (node (ref "X1") (pin "2") (pinfunction "2_2") (pintype "passive"))
      (node (ref "X1") (pin "4") (pinfunction "4_4") (pintype "passive"))
    )
    (net (code "15") (name "HAPTIC_EN") (class "Default")
      (node (ref "IC4") (pin "A1") (pinfunction "EN_A1") (pintype "bidirectional"))
      (node (ref "P1.01/2.4B") (pin "P$U1") (pinfunction "P0.12_P$U1") (pintype "bidirectional"))
    )
    (net (code "16") (name "IMU_INT1") (class "Default")
      (node (ref "IC3") (pin "5") (pinfunction "INT1_5") (pintype "bidirectional"))
      (node (ref "P1.01/2.4B") (pin "P$N1") (pinfunction "P0.08_P$N1") (pintype "bidirectional"))
    )
    (net (code "17") (name "IMU_INT2") (class "Default")
      (node (ref "IC3") (pin "6") (pinfunction "INT2_6") (pintype "bidirectional"))
      (node (ref "P1.01/2.4B") (pin "P$P2") (pinfunction "P1.08_P$P2") (pintype "bidirectional"))
    )
    (net (code "18") (name "LX1") (class "Default")
      (node (ref "IC2") (pin "B2") (pinfunction "SW1_1_B2") (pintype "bidirectional"))
      (node (ref "IC2") (pin "B3") (pinfunction "SW1_2_B3") (pintype "bidirectional"))
      (node (ref "L1") (pin "1") (pinfunction "1_1") (pintype "bidirectional"))
    )
    (net (code "19") (name "LX2") (class "Default")
      (node (ref "IC2") (pin "D2") (pinfunction "SW2_1_D2") (pintype "bidirectional"))
      (node (ref "IC2") (pin "D3") (pinfunction "SW2_2_D3") (pintype "bidirectional"))
      (node (ref "L1") (pin "2") (pinfunction "2_2") (pintype "bidirectional"))
    )
    (net (code "20") (name "MOSI") (class "Default")
      (node (ref "J2") (pin "14") (pinfunction "14_14") (pintype "bidirectional"))
      (node (ref "P1.01/2.4B") (pin "P$B13") (pinfunction "P0.03/AIN1_P$B13") (pintype "bidirectional"))
    )
    (net (code "21") (name "Net-(ANT1-FEED)") (class "Default")
      (node (ref "ANT1") (pin "1") (pinfunction "FEED_1") (pintype "input"))
      (node (ref "CC22") (pin "2") (pinfunction "2_2") (pintype "passive"))
      (node (ref "CC4") (pin "2") (pinfunction "2_2") (pintype "passive"))
      (node (ref "LL1") (pin "2") (pinfunction "2_2") (pintype "passive"))
    )
    (net (code "22") (name "Net-(C5-Pad2)") (class "Default")
      (node (ref "C5") (pin "2") (pinfunction "2_2") (pintype "passive"))
      (node (ref "R11") (pin "1") (pinfunction "1_1") (pintype "bidirectional"))
    )
    (net (code "23") (name "Net-(C10-Pad2)") (class "Default")
      (node (ref "C10") (pin "2") (pinfunction "2_2") (pintype "passive"))
      (node (ref "R12") (pin "1") (pinfunction "1_1") (pintype "bidirectional"))
    )
    (net (code "24") (name "Net-(C11-Pad2)") (class "Default")
      (node (ref "C11") (pin "2") (pinfunction "2_2") (pintype "passive"))
      (node (ref "R13") (pin "1") (pinfunction "1_1") (pintype "bidirectional"))
    )
    (net (code "25") (name "Net-(C12-Pad1)") (class "Default")
      (node (ref "C12") (pin "1") (pinfunction "1_1") (pintype "passive"))
      (node (ref "P1.01/2.4B") (pin "P$A22") (pinfunction "VDD_P$A22") (pintype "power_in"))
    )
    (net (code "26") (name "Net-(D1-K)") (class "Default")
      (node (ref "C2-EP-DR") (pin "1") (pinfunction "1_1") (pintype "passive"))
      (node (ref "D1") (pin "1") (pinfunction "K_1") (pintype "bidirectional"))
      (node (ref "D2") (pin "2") (pinfunction "A_2") (pintype "bidirectional"))
    )
    (net (code "27") (name "Net-(D3-A)") (class "Default")
      (node (ref "C2-EP-DR") (pin "2") (pinfunction "2_2") (pintype "passive"))
      (node (ref "D3") (pin "2") (pinfunction "A_2") (pintype "bidirectional"))
      (node (ref "L2") (pin "1") (pinfunction "1_1") (pintype "passive"))
      (node (ref "Q2") (pin "3") (pinfunction "D_3") (pintype "bidirectional"))
    )
    (net (code "28") (name "Net-(EPD_C1-Pad2)") (class "Default")
      (node (ref "EPD_C1") (pin "2") (pinfunction "2_2") (pintype "passive"))
      (node (ref "J2") (pin "5") (pinfunction "5_5") (pintype "bidirectional"))
    )
    (net (code "29") (name "Net-(EPD_C2-Pad2)") (class "Default")
      (node (ref "EPD_C2") (pin "2") (pinfunction "2_2") (pintype "passive"))
      (node (ref "J2") (pin "4") (pinfunction "4_4") (pintype "bidirectional"))
    )
    (net (code "30") (name "Net-(EPD_C6-Pad2)") (class "Default")
      (node (ref "EPD_C6") (pin "2") (pinfunction "2_2") (pintype "passive"))
      (node (ref "J2") (pin "18") (pinfunction "18_18") (pintype "bidirectional"))
    )
    (net (code "31") (name "Net-(EPD_C7-Pad2)") (class "Default")
      (node (ref "EPD_C7") (pin "2") (pinfunction "2_2") (pintype "passive"))
      (node (ref "J2") (pin "19") (pinfunction "19_19") (pintype "bidirectional"))
    )
    (net (code "32") (name "Net-(EPD_C8-Pad2)") (class "Default")
      (node (ref "EPD_C8") (pin "2") (pinfunction "2_2") (pintype "passive"))
      (node (ref "J2") (pin "20") (pinfunction "20_20") (pintype "bidirectional"))
    )
    (net (code "33") (name "Net-(EPD_C10-Pad2)") (class "Default")
      (node (ref "EPD_C10") (pin "2") (pinfunction "2_2") (pintype "passive"))
      (node (ref "J2") (pin "22") (pinfunction "22_22") (pintype "bidirectional"))
    )
    (net (code "34") (name "Net-(EPD_C12-Pad2)") (class "Default")
      (node (ref "EPD_C12") (pin "2") (pinfunction "2_2") (pintype "passive"))
      (node (ref "J2") (pin "24") (pinfunction "24_24") (pintype "bidirectional"))
    )
    (net (code "35") (name "Net-(IC1-TS{slash}MR)") (class "Default")
      (node (ref "IC1") (pin "D1") (pinfunction "TS/MR_D1") (pintype "bidirectional"))
      (node (ref "R1") (pin "2") (pinfunction "2_2") (pintype "bidirectional"))
    )
    (net (code "36") (name "Net-(IC2-SCL)") (class "Default")
      (node (ref "IC2") (pin "D1") (pinfunction "SCL_D1") (pintype "bidirectional"))
      (node (ref "R2") (pin "2") (pinfunction "2_2") (pintype "bidirectional"))
    )
    (net (code "37") (name "Net-(IC2-SDA)") (class "Default")
      (node (ref "IC2") (pin "E1") (pinfunction "SDA_E1") (pintype "bidirectional"))
      (node (ref "R3") (pin "2") (pinfunction "2_2") (pintype "bidirectional"))
    )
    (net (code "38") (name "Net-(IC3-SDO)") (class "Default")
      (node (ref "IC3") (pin "1") (pinfunction "SDO_1") (pintype "bidirectional"))
      (node (ref "R8") (pin "1") (pinfunction "1_1") (pintype "bidirectional"))
    )
    (net (code "39") (name "Net-(IC4-REG)") (class "Default")
      (node (ref "C3") (pin "2") (pinfunction "2_2") (pintype "passive"))
      (node (ref "IC4") (pin "A2") (pinfunction "REG_A2") (pintype "bidirectional"))
    )
    (net (code "40") (name "Net-(J3-CC1)") (class "Default")
      (node (ref "J3") (pin "A5") (pinfunction "CC1_A5") (pintype "bidirectional"))
      (node (ref "R14") (pin "1") (pinfunction "1_1") (pintype "bidirectional"))
    )
    (net (code "41") (name "Net-(J3-CC2)") (class "Default")
      (node (ref "J3") (pin "B5") (pinfunction "CC2_B5") (pintype "bidirectional"))
      (node (ref "R15") (pin "2") (pinfunction "2_2") (pintype "bidirectional"))
    )
    (net (code "42") (name "Net-(LL2-Pad1)") (class "Default")
      (node (ref "LL2") (pin "1") (pinfunction "1_1") (pintype "passive"))
      (node (ref "LL3") (pin "2") (pinfunction "2_2") (pintype "passive"))
    )
    (net (code "43") (name "Net-(P1.01/2.4B-ANT)") (class "Default")
      (node (ref "CC3") (pin "2") (pinfunction "2_2") (pintype "passive"))
      (node (ref "LL1") (pin "1") (pinfunction "1_1") (pintype "passive"))
      (node (ref "P1.01/2.4B") (pin "P$H23") (pinfunction "ANT_P$H23") (pintype "bidirectional"))
    )
    (net (code "44") (name "Net-(P1.01/2.4B-DCC)") (class "Default")
      (node (ref "LL2") (pin "2") (pinfunction "2_2") (pintype "passive"))
      (node (ref "P1.01/2.4B") (pin "P$B3") (pinfunction "DCC_P$B3") (pintype "output"))
    )
    (net (code "45") (name "Net-(P1.01/2.4B-DEC1)") (class "Default")
      (node (ref "CC5") (pin "2") (pinfunction "2_2") (pintype "passive"))
      (node (ref "P1.01/2.4B") (pin "P$C1") (pinfunction "DEC1_P$C1") (pintype "power_in"))
    )
    (net (code "46") (name "Net-(P1.01/2.4B-DEC2)") (class "Default")
      (node (ref "C13") (pin "1") (pinfunction "1_1") (pintype "passive"))
      (node (ref "P1.01/2.4B") (pin "P$A18") (pinfunction "DEC2_P$A18") (pintype "bidirectional"))
    )
    (net (code "47") (name "Net-(P1.01/2.4B-DEC3)") (class "Default")
      (node (ref "CC11") (pin "1") (pinfunction "1_1") (pintype "passive"))
      (node (ref "P1.01/2.4B") (pin "P$D23") (pinfunction "DEC3_P$D23") (pintype "bidirectional"))
    )
    (net (code "48") (name "Net-(P1.01/2.4B-DEC3V3)") (class "Default")
      (node (ref "C20") (pin "2") (pinfunction "2_2") (pintype "passive"))
      (node (ref "P1.01/2.4B") (pin "P$AC5") (pinfunction "DEC3V3_P$AC5") (pintype "bidirectional"))
    )
    (net (code "49") (name "Net-(P1.01/2.4B-DEC4)") (class "Default")
      (node (ref "C15") (pin "1") (pinfunction "1_1") (pintype "passive"))
      (node (ref "C16") (pin "1") (pinfunction "1_1") (pintype "passive"))
      (node (ref "CC10") (pin "1") (pinfunction "1_1") (pintype "passive"))
      (node (ref "LL3") (pin "1") (pinfunction "1_1") (pintype "passive"))
      (node (ref "P1.01/2.4B") (pin "P$B5") (pinfunction "DEC4_P$B5") (pintype "power_in"))
      (node (ref "P1.01/2.4B") (pin "P$E24") (pinfunction "DEC6_P$E24") (pintype "bidirectional"))
    )
    (net (code "50") (name "Net-(P1.01/2.4B-DEC5)") (class "Default")
      (node (ref "C9") (pin "1") (pinfunction "1_1") (pintype "passive"))
      (node (ref "P1.01/2.4B") (pin "P$N24") (pinfunction "DEC5_P$N24") (pintype "bidirectional"))
    )
    (net (code "51") (name "Net-(P1.01/2.4B-P0.00{slash}XL1)") (class "Default")
      (node (ref "C17") (pin "1") (pinfunction "1_1") (pintype "passive"))
      (node (ref "P1.01/2.4B") (pin "P$D2") (pinfunction "P0.00/XL1_P$D2") (pintype "bidirectional"))
      (node (ref "X2") (pin "2") (pinfunction "2_2") (pintype "passive"))
    )
    (net (code "52") (name "Net-(P1.01/2.4B-P0.01{slash}XL2)") (class "Default")
      (node (ref "C18") (pin "1") (pinfunction "1_1") (pintype "passive"))
      (node (ref "P1.01/2.4B") (pin "P$F2") (pinfunction "P0.01/XL2_P$F2") (pintype "bidirectional"))
      (node (ref "X2") (pin "1") (pinfunction "1_1") (pintype "passive"))
    )
    (net (code "53") (name "Net-(P1.01/2.4B-XC1)") (class "Default")
      (node (ref "CC1") (pin "1") (pinfunction "1_1") (pintype "passive"))
      (node (ref "P1.01/2.4B") (pin "P$B24") (pinfunction "XC1_P$B24") (pintype "input"))
      (node (ref "X1") (pin "1") (pinfunction "1_1") (pintype "passive"))
    )
    (net (code "54") (name "Net-(P1.01/2.4B-XC2)") (class "Default")
      (node (ref "CC2") (pin "1") (pinfunction "1_1") (pintype "passive"))
      (node (ref "P1.01/2.4B") (pin "P$A23") (pinfunction "XC2_P$A23") (pintype "output"))
      (node (ref "X1") (pin "3") (pinfunction "3_3") (pintype "passive"))
    )
    (net (code "55") (name "Net-(Q2-S)") (class "Default")
      (node (ref "Q2") (pin "2") (pinfunction "S_2") (pintype "bidirectional"))
      (node (ref "R9") (pin "2") (pinfunction "2_2") (pintype "bidirectional"))
    )
    (net (code "56") (name "Net-(R10-Pad2)") (class "Default")
      (node (ref "R10") (pin "2") (pinfunction "2_2") (pintype "bidirectional"))
      (node (ref "R9") (pin "1") (pinfunction "1_1") (pintype "bidirectional"))
      (node (ref "SJ1") (pin "2") (pinfunction "2_2") (pintype "passive"))
    )
    (net (code "57") (name "OUT+") (class "Default")
      (node (ref "IC4") (pin "A3") (pinfunction "OUT+_A3") (pintype "bidirectional"))
      (node (ref "TP_SDA7") (pin "TP") (pinfunction "TP_TP") (pintype "input"))
    )
    (net (code "58") (name "OUT-") (class "Default")
      (node (ref "IC4") (pin "C3") (pinfunction "OUT-_C3") (pintype "bidirectional"))
      (node (ref "TP_SDA8") (pin "TP") (pinfunction "TP_TP") (pintype "input"))
    )
    (net (code "59") (name "P0.04") (class "Default")
      (node (ref "P1.01/2.4B") (pin "P$J1") (pinfunction "P0.04/AIN2_P$J1") (pintype "bidirectional"))
    )
    (net (code "60") (name "P0.09") (class "Default")
      (node (ref "P1.01/2.4B") (pin "P$L24") (pinfunction "P0.09/NFC1_P$L24") (pintype "bidirectional"))
    )
    (net (code "61") (name "P0.13") (class "Default")
      (node (ref "P1.01/2.4B") (pin "P$AD8") (pinfunction "P0.13_P$AD8") (pintype "bidirectional"))
      (node (ref "SW1") (pin "2") (pinfunction "2_2") (pintype "passive"))
    )
    (net (code "62") (name "P0.14") (class "Default")
      (node (ref "P1.01/2.4B") (pin "P$AC9") (pinfunction "P0.14_P$AC9") (pintype "bidirectional"))
      (node (ref "SW2") (pin "2") (pinfunction "2_2") (pintype "passive"))
    )
    (net (code "63") (name "P0.19") (class "Default")
      (node (ref "P1.01/2.4B") (pin "P$AC15") (pinfunction "P0.19_P$AC15") (pintype "bidirectional"))
    )
    (net (code "64") (name "P0.20") (class "Default")
      (node (ref "P1.01/2.4B") (pin "P$AD16") (pinfunction "P0.20_P$AD16") (pintype "bidirectional"))
    )
    (net (code "65") (name "P0.21") (class "Default")
      (node (ref "P1.01/2.4B") (pin "P$AC17") (pinfunction "P0.21_P$AC17") (pintype "bidirectional"))
    )
    (net (code "66") (name "P0.22") (class "Default")
      (node (ref "P1.01/2.4B") (pin "P$AD18") (pinfunction "P0.22_P$AD18") (pintype "bidirectional"))
    )
    (net (code "67") (name "P0.23") (class "Default")
      (node (ref "P1.01/2.4B") (pin "P$AC19") (pinfunction "P0.23_P$AC19") (pintype "bidirectional"))
    )
    (net (code "68") (name "P0.24") (class "Default")
      (node (ref "P1.01/2.4B") (pin "P$AD20") (pinfunction "P0.24_P$AD20") (pintype "bidirectional"))
    )
    (net (code "69") (name "P0.25") (class "Default")
      (node (ref "P1.01/2.4B") (pin "P$AC21") (pinfunction "P0.25_P$AC21") (pintype "bidirectional"))
    )
    (net (code "70") (name "P0.26") (class "Default")
      (node (ref "P1.01/2.4B") (pin "P$G1") (pinfunction "P0.26_P$G1") (pintype "bidirectional"))
    )
    (net (code "71") (name "P0.27") (class "Default")
      (node (ref "P1.01/2.4B") (pin "P$H2") (pinfunction "P0.27_P$H2") (pintype "bidirectional"))
    )
    (net (code "72") (name "P0.28") (class "Default")
      (node (ref "P1.01/2.4B") (pin "P$B11") (pinfunction "P0.28/AIN4_P$B11") (pintype "bidirectional"))
    )
    (net (code "73") (name "P0.29") (class "Default")
      (node (ref "P1.01/2.4B") (pin "P$A10") (pinfunction "P0.29/AIN5_P$A10") (pintype "bidirectional"))
    )
    (net (code "74") (name "P0.30") (class "Default")
      (node (ref "P1.01/2.4B") (pin "P$B9") (pinfunction "P0.30/AIN6_P$B9") (pintype "bidirectional"))
    )
    (net (code "75") (name "P0.31") (class "Default")
      (node (ref "P1.01/2.4B") (pin "P$A8") (pinfunction "P0.31/AIN7_P$A8") (pintype "bidirectional"))
    )
    (net (code "76") (name "P1.01") (class "Default")
      (node (ref "P1.01/2.4B") (pin "P$Y23") (pinfunction "P1.01_P$Y23") (pintype "bidirectional"))
      (node (ref "Q1") (pin "1") (pinfunction "G_1") (pintype "bidirectional"))
      (node (ref "R7") (pin "1") (pinfunction "1_1") (pintype "bidirectional"))
    )
    (net (code "77") (name "P1.02") (class "Default")
      (node (ref "P1.01/2.4B") (pin "P$W24") (pinfunction "P1.02_P$W24") (pintype "bidirectional"))
      (node (ref "SW3") (pin "2") (pinfunction "2_2") (pintype "passive"))
    )
    (net (code "78") (name "P1.03") (class "Default")
      (node (ref "P1.01/2.4B") (pin "P$V23") (pinfunction "P1.03_P$V23") (pintype "bidirectional"))
    )
    (net (code "79") (name "P1.04") (class "Default")
      (node (ref "P1.01/2.4B") (pin "P$U24") (pinfunction "P1.04_P$U24") (pintype "bidirectional"))
    )
    (net (code "80") (name "P1.05") (class "Default")
      (node (ref "P1.01/2.4B") (pin "P$T23") (pinfunction "P1.05_P$T23") (pintype "bidirectional"))
    )
    (net (code "81") (name "P1.06") (class "Default")
      (node (ref "P1.01/2.4B") (pin "P$R24") (pinfunction "P1.06_P$R24") (pintype "bidirectional"))
    )
    (net (code "82") (name "P1.07") (class "Default")
      (node (ref "P1.01/2.4B") (pin "P$P23") (pinfunction "P1.07_P$P23") (pintype "bidirectional"))
    )
    (net (code "83") (name "P1.09") (class "Default")
      (node (ref "P1.01/2.4B") (pin "P$R1") (pinfunction "P1.09_P$R1") (pintype "bidirectional"))
    )
    (net (code "84") (name "P1.10") (class "Default")
      (node (ref "P1.01/2.4B") (pin "P$A20") (pinfunction "P1.10_P$A20") (pintype "bidirectional"))
    )
    (net (code "85") (name "P1.11") (class "Default")
      (node (ref "P1.01/2.4B") (pin "P$B19") (pinfunction "P1.11_P$B19") (pintype "bidirectional"))
    )
    (net (code "86") (name "P1.12") (class "Default")
      (node (ref "P1.01/2.4B") (pin "P$B17") (pinfunction "P1.12_P$B17") (pintype "bidirectional"))
    )
    (net (code "87") (name "P1.13") (class "Default")
      (node (ref "P1.01/2.4B") (pin "P$A16") (pinfunction "P1.13_P$A16") (pintype "bidirectional"))
    )
    (net (code "88") (name "P1.14") (class "Default")
      (node (ref "P1.01/2.4B") (pin "P$B15") (pinfunction "P1.14_P$B15") (pintype "bidirectional"))
    )
    (net (code "89") (name "P1.15") (class "Default")
      (node (ref "P1.01/2.4B") (pin "P$A14") (pinfunction "P1.15_P$A14") (pintype "bidirectional"))
    )
    (net (code "90") (name "PMIC_INT") (class "Default")
      (node (ref "IC1") (pin "A1") (pinfunction "~{INT}_A1") (pintype "bidirectional"))
      (node (ref "P1.01/2.4B") (pin "P$T2") (pinfunction "P0.11_P$T2") (pintype "bidirectional"))
    )
    (net (code "91") (name "PREVGH") (class "Default")
      (node (ref "D3") (pin "1") (pinfunction "K_1") (pintype "bidirectional"))
      (node (ref "EPD_C9") (pin "2") (pinfunction "2_2") (pintype "passive"))
      (node (ref "J2") (pin "21") (pinfunction "21_21") (pintype "bidirectional"))
    )
    (net (code "92") (name "PREVGL") (class "Default")
      (node (ref "D1") (pin "2") (pinfunction "A_2") (pintype "bidirectional"))
      (node (ref "EPD_C11") (pin "2") (pinfunction "2_2") (pintype "passive"))
      (node (ref "J2") (pin "23") (pinfunction "23_23") (pintype "bidirectional"))
    )
    (net (code "93") (name "RESE") (class "Default")
      (node (ref "J2") (pin "3") (pinfunction "3_3") (pintype "bidirectional"))
    )
    (net (code "94") (name "RESET") (class "Default")
      (node (ref "J1") (pin "6") (pinfunction "6_6") (pintype "bidirectional"))
      (node (ref "P1.01/2.4B") (pin "P$AC13") (pinfunction "P0.18/RESET_P$AC13") (pintype "bidirectional"))
      (node (ref "TP_SDA4") (pin "TP") (pinfunction "TP_TP") (pintype "input"))
    )
    (net (code "95") (name "SCK") (class "Default")
      (node (ref "J2") (pin "13") (pinfunction "13_13") (pintype "bidirectional"))
      (node (ref "P1.01/2.4B") (pin "P$A12") (pinfunction "P0.02/AIN0_P$A12") (pintype "bidirectional"))
    )
    (net (code "96") (name "SCL{slash}1.4C") (class "Default")
      (node (ref "IC4") (pin "C1") (pinfunction "SCL_C1") (pintype "bidirectional"))
      (node (ref "U1") (pin "7") (pinfunction "SCL_7") (pintype "input"))
    )
    (net (code "97") (name "SCL{slash}2.4C") (class "Default")
      (node (ref "IC1") (pin "B1") (pinfunction "SCL_B1") (pintype "bidirectional"))
      (node (ref "IC3") (pin "12") (pinfunction "SCX_12") (pintype "bidirectional"))
      (node (ref "P1.01/2.4B") (pin "P$M2") (pinfunction "P0.07_P$M2") (pintype "bidirectional"))
      (node (ref "R2") (pin "1") (pinfunction "1_1") (pintype "bidirectional"))
      (node (ref "R4") (pin "1") (pinfunction "1_1") (pintype "bidirectional"))
      (node (ref "TP_SCL") (pin "TP") (pinfunction "TP_TP") (pintype "input"))
    )
    (net (code "98") (name "SDA{slash}1.4C") (class "Default")
      (node (ref "IC4") (pin "B2") (pinfunction "SDA_B2") (pintype "bidirectional"))
      (node (ref "U1") (pin "8") (pinfunction "SDA_8") (pintype "bidirectional"))
    )
    (net (code "99") (name "SDA{slash}2.4C") (class "Default")
      (node (ref "IC1") (pin "C1") (pinfunction "SDA_C1") (pintype "bidirectional"))
      (node (ref "IC3") (pin "2") (pinfunction "SDX_2") (pintype "bidirectional"))
      (node (ref "P1.01/2.4B") (pin "P$L1") (pinfunction "P0.06_P$L1") (pintype "bidirectional"))
      (node (ref "R3") (pin "1") (pinfunction "1_1") (pintype "bidirectional"))
      (node (ref "R5") (pin "1") (pinfunction "1_1") (pintype "bidirectional"))
      (node (ref "TP_SDA") (pin "TP") (pinfunction "TP_TP") (pintype "input"))
    )
    (net (code "100") (name "SWDCLK") (class "Default")
      (node (ref "J1") (pin "4") (pinfunction "4_4") (pintype "bidirectional"))
      (node (ref "P1.01/2.4B") (pin "P$AA24") (pinfunction "SWDCLK_P$AA24") (pintype "input"))
      (node (ref "TP_SDA3") (pin "TP") (pinfunction "TP_TP") (pintype "input"))
    )
    (net (code "101") (name "SWDIO") (class "Default")
      (node (ref "J1") (pin "2") (pinfunction "2_2") (pintype "bidirectional"))
      (node (ref "P1.01/2.4B") (pin "P$AC24") (pinfunction "SWDIO_P$AC24") (pintype "bidirectional"))
      (node (ref "TP_SDA2") (pin "TP") (pinfunction "TP_TP") (pintype "input"))
    )
    (net (code "102") (name "SWO") (class "Default")
      (node (ref "P1.01/2.4B") (pin "P$AD22") (pinfunction "P1.00_P$AD22") (pintype "bidirectional"))
      (node (ref "TP_SDA1") (pin "TP") (pinfunction "TP_TP") (pintype "input"))
    )
    (net (code "103") (name "VBAT{slash}1.2A") (class "Default")
      (node (ref "C2") (pin "2") (pinfunction "2_2") (pintype "passive"))
      (node (ref "TP_SDA9") (pin "TP") (pinfunction "TP_TP") (pintype "input"))
      (node (ref "U1") (pin "2") (pinfunction "CELL_2") (pintype "power_in"))
      (node (ref "U1") (pin "3") (pinfunction "VDD_3") (pintype "power_in"))
    )
    (net (code "104") (name "VBAT{slash}2.5C") (class "Default")
      (node (ref "C37") (pin "1") (pinfunction "1_1") (pintype "passive"))
      (node (ref "IC1") (pin "C2") (pinfunction "BAT_C2") (pintype "bidirectional"))
    )
    (net (code "105") (name "VBUS{slash}1.5D") (class "Default")
      (node (ref "C42") (pin "2") (pinfunction "2_2") (pintype "passive"))
      (node (ref "C43") (pin "1") (pinfunction "1_1") (pintype "passive"))
      (node (ref "D4") (pin "5") (pinfunction "VBUS_5") (pintype "bidirectional"))
      (node (ref "J3") (pin "A4_B9") (pinfunction "VBUS_A4_B9") (pintype "power_in"))
      (node (ref "J3") (pin "A9_B4") (pinfunction "VBUS_A9_B4") (pintype "power_in"))
    )
    (net (code "106") (name "VBUS{slash}2.6D") (class "Default")
      (node (ref "C21") (pin "1") (pinfunction "1_1") (pintype "passive"))
      (node (ref "C38") (pin "1") (pinfunction "1_1") (pintype "passive"))
      (node (ref "IC1") (pin "A2") (pinfunction "IN_A2") (pintype "bidirectional"))
      (node (ref "P1.01/2.4B") (pin "P$AD2") (pinfunction "VBUS_P$AD2") (pintype "power_in"))
    )
    (net (code "107") (name "VREG") (class "Default")
      (node (ref "C23") (pin "2") (pinfunction "2_2") (pintype "passive"))
      (node (ref "C24") (pin "2") (pinfunction "2_2") (pintype "passive"))
      (node (ref "C39") (pin "1") (pinfunction "1_1") (pintype "passive"))
      (node (ref "IC1") (pin "B2") (pinfunction "SYS_B2") (pintype "bidirectional"))
      (node (ref "IC2") (pin "A1") (pinfunction "EN_A1") (pintype "bidirectional"))
      (node (ref "IC2") (pin "A2") (pinfunction "VIN_1_A2") (pintype "bidirectional"))
      (node (ref "IC2") (pin "A3") (pinfunction "VIN_2_A3") (pintype "bidirectional"))
      (node (ref "TP_VREG") (pin "TP") (pinfunction "TP_TP") (pintype "input"))
    )
    (net (code "108") (name "unconnected-(ANT1-NC-Pad2)") (class "Default")
      (node (ref "ANT1") (pin "2") (pinfunction "NC_2") (pintype "no_connect"))
    )
    (net (code "109") (name "unconnected-(IC3-ASCL-Pad11)") (class "Default")
      (node (ref "IC3") (pin "11") (pinfunction "ASCL_11") (pintype "bidirectional"))
    )
    (net (code "110") (name "unconnected-(IC3-ASDA-Pad4)") (class "Default")
      (node (ref "IC3") (pin "4") (pinfunction "ASDA_4") (pintype "bidirectional"))
    )
    (net (code "111") (name "unconnected-(J2-Pad1)") (class "Default")
      (node (ref "J2") (pin "1") (pinfunction "1_1") (pintype "bidirectional"))
    )
    (net (code "112") (name "unconnected-(J2-Pad6)") (class "Default")
      (node (ref "J2") (pin "6") (pinfunction "6_6") (pintype "bidirectional"))
    )
    (net (code "113") (name "unconnected-(J2-Pad7)") (class "Default")
      (node (ref "J2") (pin "7") (pinfunction "7_7") (pintype "bidirectional"))
    )
    (net (code "114") (name "unconnected-(J3-SBU1-PadA8)") (class "Default")
      (node (ref "J3") (pin "A8") (pinfunction "SBU1_A8") (pintype "bidirectional"))
    )
    (net (code "115") (name "unconnected-(J3-SBU2-PadB8)") (class "Default")
      (node (ref "J3") (pin "B8") (pinfunction "SBU2_B8") (pintype "bidirectional"))
    )
    (net (code "116") (name "unconnected-(P1.01/2.4B-DCCH-PadP$AB2)") (class "Default")
      (node (ref "P1.01/2.4B") (pin "P$AB2") (pinfunction "DCCH_P$AB2") (pintype "bidirectional"))
    )
  )
)
